# SK_MFB.net
KiCad netlist of a schematic drawn in EasyEDA Pro
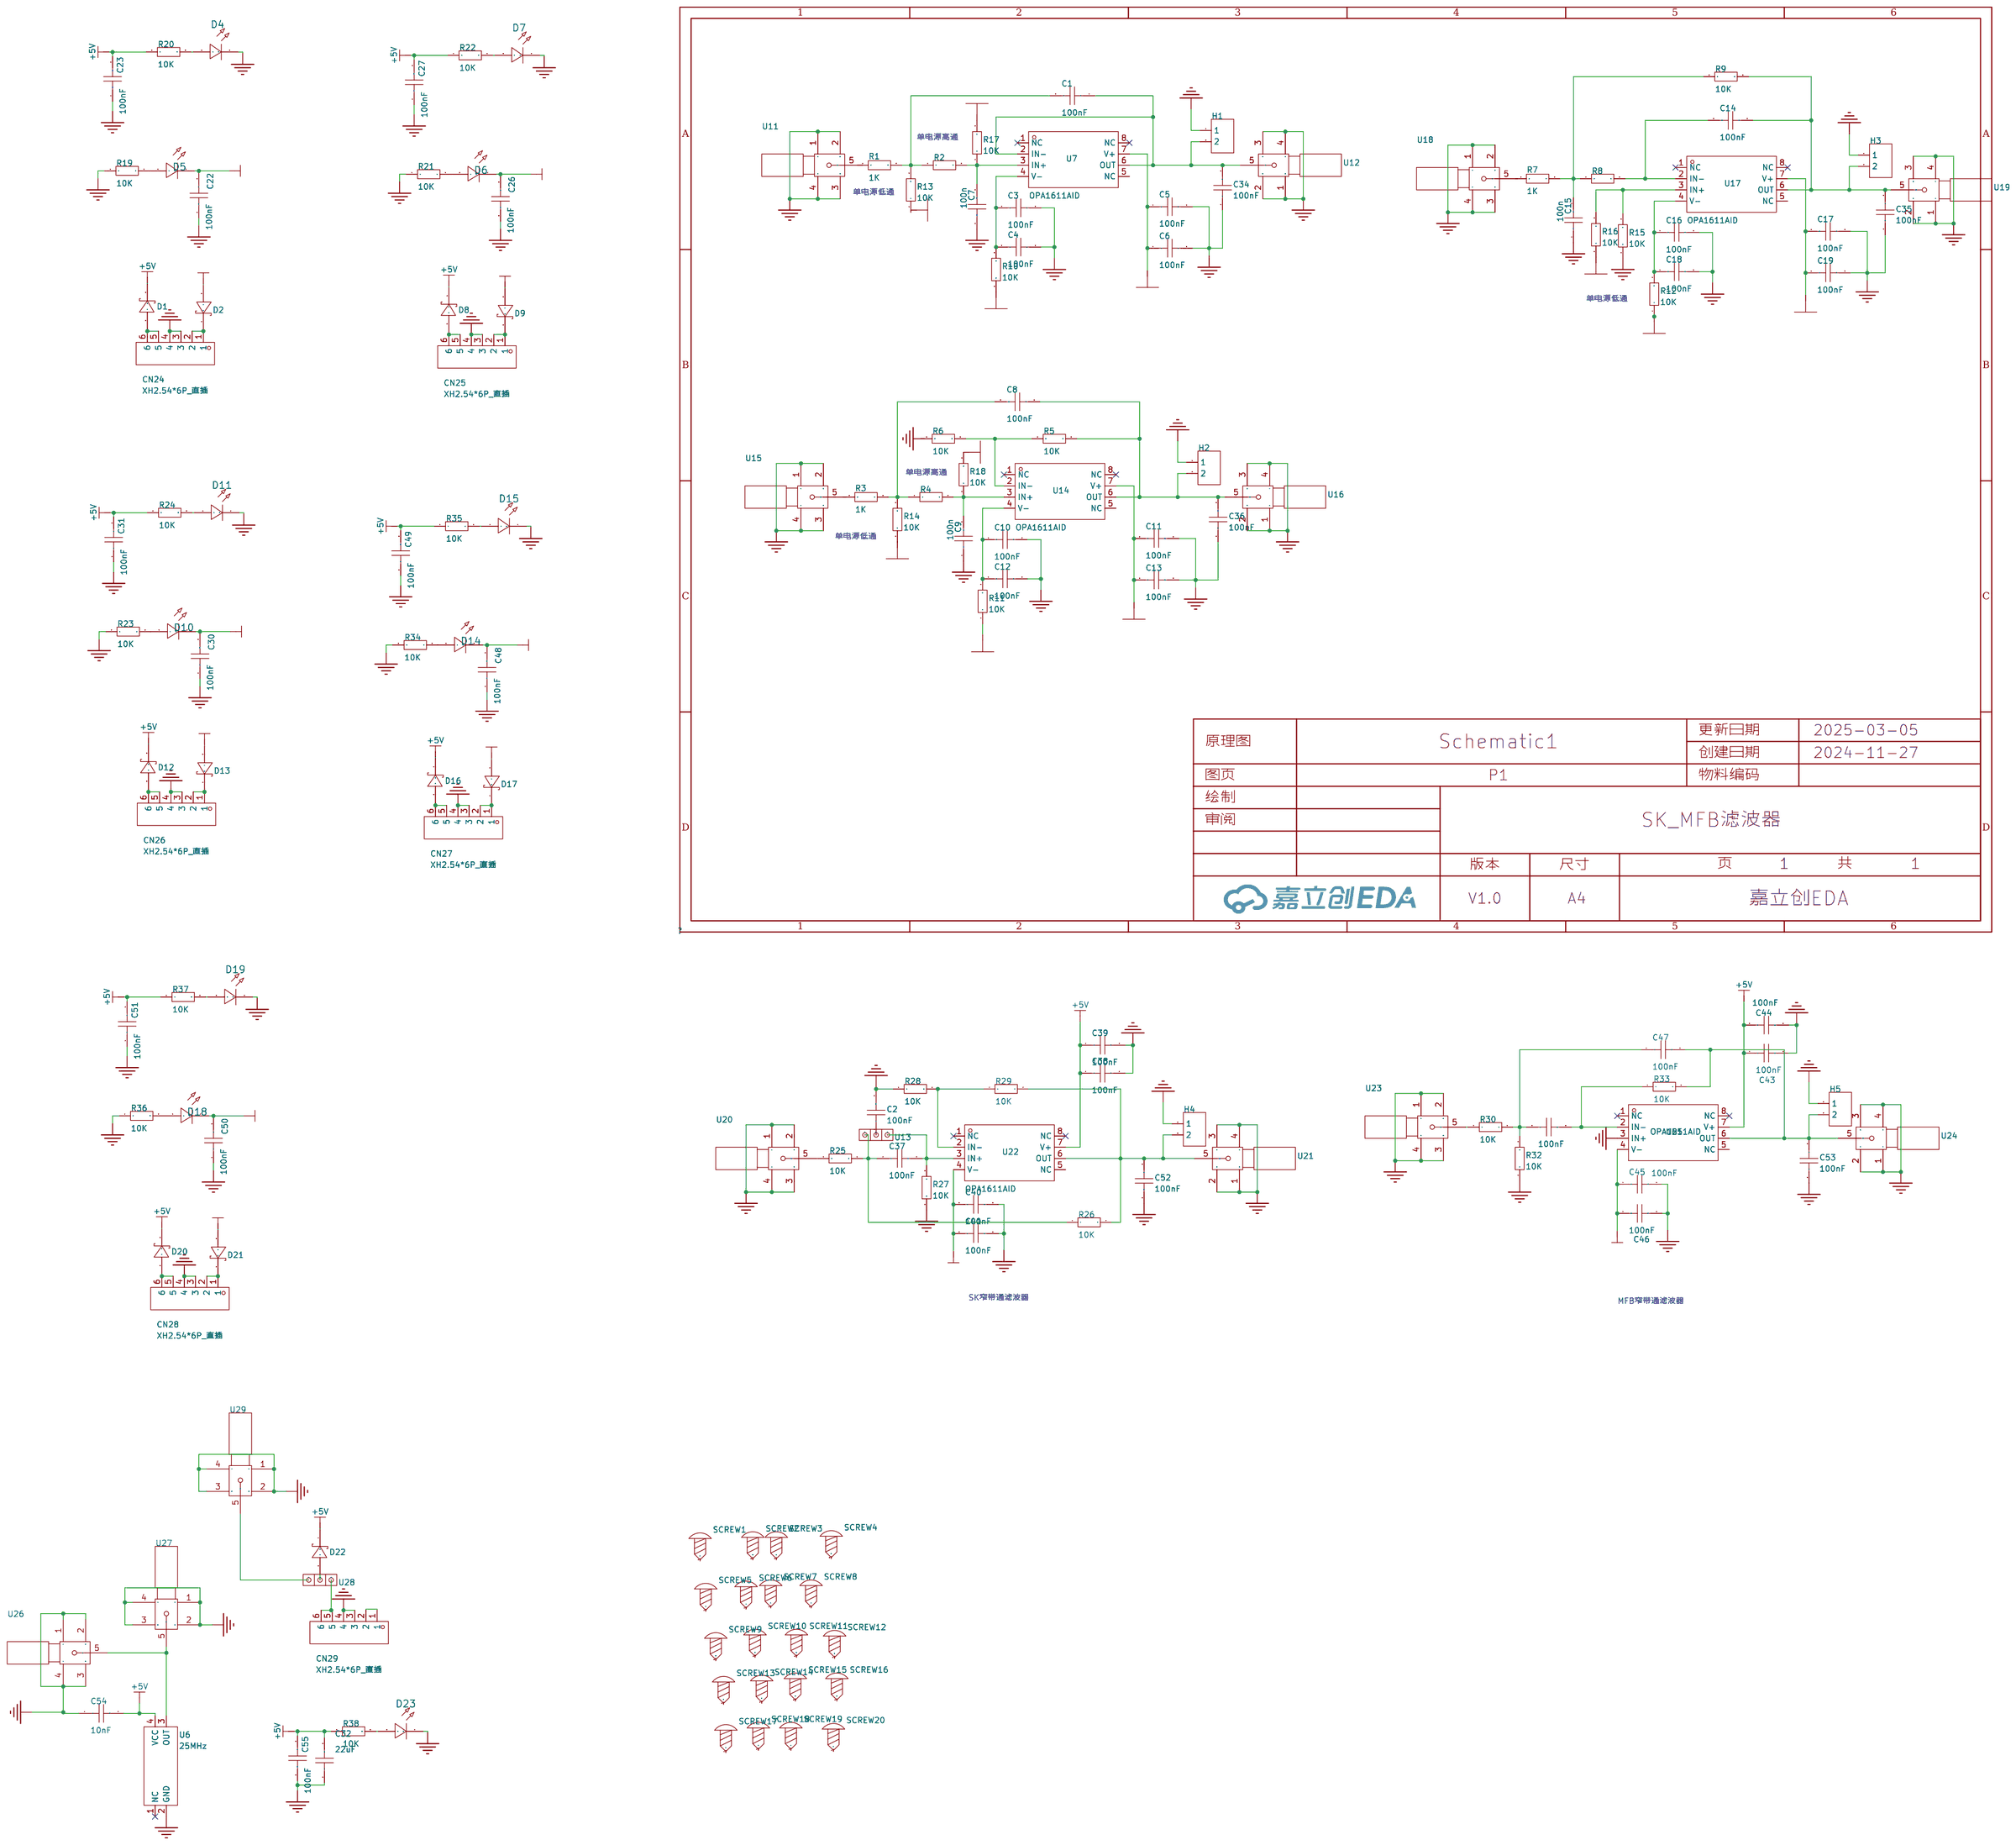
[diagram p0: schematic sheet]

(export (version "E")
  (design (tool "Eeschema 10.0.6"))
  (components
    (comp (ref "C1")
      (value "100nF")
      (footprint "easyedapro:C0805")
      (libsource (lib "easyedapro") (part "CapAcitance"))
    )
    (comp (ref "C2")
      (value "100nF")
      (footprint "easyedapro:C0805")
      (libsource (lib "easyedapro") (part "CapAcitance"))
    )
    (comp (ref "C3")
      (value "100nF")
      (footprint "easyedapro:C0805")
      (libsource (lib "easyedapro") (part "CapAcitance"))
    )
    (comp (ref "C4")
      (value "100nF")
      (footprint "easyedapro:C0805")
      (libsource (lib "easyedapro") (part "CapAcitance"))
    )
    (comp (ref "C5")
      (value "100nF")
      (footprint "easyedapro:C0805")
      (libsource (lib "easyedapro") (part "CapAcitance"))
    )
    (comp (ref "C6")
      (value "100nF")
      (footprint "easyedapro:C0805")
      (libsource (lib "easyedapro") (part "CapAcitance"))
    )
    (comp (ref "C7")
      (value "100n")
      (footprint "easyedapro:C0805")
      (libsource (lib "easyedapro") (part "CapAcitance"))
    )
    (comp (ref "C8")
      (value "100nF")
      (footprint "easyedapro:C0805")
      (libsource (lib "easyedapro") (part "CapAcitance"))
    )
    (comp (ref "C9")
      (value "100n")
      (footprint "easyedapro:C0805")
      (libsource (lib "easyedapro") (part "CapAcitance"))
    )
    (comp (ref "C10")
      (value "100nF")
      (footprint "easyedapro:C0805")
      (libsource (lib "easyedapro") (part "CapAcitance"))
    )
    (comp (ref "C11")
      (value "100nF")
      (footprint "easyedapro:C0805")
      (libsource (lib "easyedapro") (part "CapAcitance"))
    )
    (comp (ref "C12")
      (value "100nF")
      (footprint "easyedapro:C0805")
      (libsource (lib "easyedapro") (part "CapAcitance"))
    )
    (comp (ref "C13")
      (value "100nF")
      (footprint "easyedapro:C0805")
      (libsource (lib "easyedapro") (part "CapAcitance"))
    )
    (comp (ref "C14")
      (value "100nF")
      (footprint "easyedapro:C0805")
      (libsource (lib "easyedapro") (part "CapAcitance"))
    )
    (comp (ref "C15")
      (value "100n")
      (footprint "easyedapro:C0805")
      (libsource (lib "easyedapro") (part "CapAcitance"))
    )
    (comp (ref "C16")
      (value "100nF")
      (footprint "easyedapro:C0805")
      (libsource (lib "easyedapro") (part "CapAcitance"))
    )
    (comp (ref "C17")
      (value "100nF")
      (footprint "easyedapro:C0805")
      (libsource (lib "easyedapro") (part "CapAcitance"))
    )
    (comp (ref "C18")
      (value "100nF")
      (footprint "easyedapro:C0805")
      (libsource (lib "easyedapro") (part "CapAcitance"))
    )
    (comp (ref "C19")
      (value "100nF")
      (footprint "easyedapro:C0805")
      (libsource (lib "easyedapro") (part "CapAcitance"))
    )
    (comp (ref "C22")
      (value "100nF")
      (footprint "easyedapro:C0805")
      (libsource (lib "easyedapro") (part "CapAcitance"))
    )
    (comp (ref "C23")
      (value "100nF")
      (footprint "easyedapro:C0805")
      (libsource (lib "easyedapro") (part "CapAcitance"))
    )
    (comp (ref "C26")
      (value "100nF")
      (footprint "easyedapro:C0805")
      (libsource (lib "easyedapro") (part "CapAcitance"))
    )
    (comp (ref "C27")
      (value "100nF")
      (footprint "easyedapro:C0805")
      (libsource (lib "easyedapro") (part "CapAcitance"))
    )
    (comp (ref "C30")
      (value "100nF")
      (footprint "easyedapro:C0805")
      (libsource (lib "easyedapro") (part "CapAcitance"))
    )
    (comp (ref "C31")
      (value "100nF")
      (footprint "easyedapro:C0805")
      (libsource (lib "easyedapro") (part "CapAcitance"))
    )
    (comp (ref "C32")
      (value "22uF")
      (footprint "easyedapro:C1210")
      (description "容值:22uF;精度:±10%;额定电压:25V;材质(温度系数):X7R;")
      (fields
        (field (name "Manufacturer Part") "CL32B226KAJNNNE")
        (field (name "Manufacturer") "SAMSUNG(三星)")
      )
      (libsource (lib "easyedapro") (part "CL32B226KAJNNNE"))
    )
    (comp (ref "C34")
      (value "100nF")
      (footprint "easyedapro:C0805")
      (libsource (lib "easyedapro") (part "CapAcitance"))
    )
    (comp (ref "C35")
      (value "100nF")
      (footprint "easyedapro:C0805")
      (libsource (lib "easyedapro") (part "CapAcitance"))
    )
    (comp (ref "C36")
      (value "100nF")
      (footprint "easyedapro:C0805")
      (libsource (lib "easyedapro") (part "CapAcitance"))
    )
    (comp (ref "C37")
      (value "100nF")
      (footprint "easyedapro:C0805")
      (libsource (lib "easyedapro") (part "CapAcitance"))
    )
    (comp (ref "C38")
      (value "100nF")
      (footprint "easyedapro:C0805")
      (libsource (lib "easyedapro") (part "CapAcitance"))
    )
    (comp (ref "C39")
      (value "100nF")
      (footprint "easyedapro:C0805")
      (libsource (lib "easyedapro") (part "CapAcitance"))
    )
    (comp (ref "C40")
      (value "100nF")
      (footprint "easyedapro:C0805")
      (libsource (lib "easyedapro") (part "CapAcitance"))
    )
    (comp (ref "C41")
      (value "100nF")
      (footprint "easyedapro:C0805")
      (libsource (lib "easyedapro") (part "CapAcitance"))
    )
    (comp (ref "C42")
      (value "100nF")
      (footprint "easyedapro:C0805")
      (libsource (lib "easyedapro") (part "CapAcitance"))
    )
    (comp (ref "C43")
      (value "100nF")
      (footprint "easyedapro:C0805")
      (libsource (lib "easyedapro") (part "CapAcitance"))
    )
    (comp (ref "C44")
      (value "100nF")
      (footprint "easyedapro:C0805")
      (libsource (lib "easyedapro") (part "CapAcitance"))
    )
    (comp (ref "C45")
      (value "100nF")
      (footprint "easyedapro:C0805")
      (libsource (lib "easyedapro") (part "CapAcitance"))
    )
    (comp (ref "C46")
      (value "100nF")
      (footprint "easyedapro:C0805")
      (libsource (lib "easyedapro") (part "CapAcitance"))
    )
    (comp (ref "C47")
      (value "100nF")
      (footprint "easyedapro:C0805")
      (libsource (lib "easyedapro") (part "CapAcitance"))
    )
    (comp (ref "C48")
      (value "100nF")
      (footprint "easyedapro:C0805")
      (libsource (lib "easyedapro") (part "CapAcitance"))
    )
    (comp (ref "C49")
      (value "100nF")
      (footprint "easyedapro:C0805")
      (libsource (lib "easyedapro") (part "CapAcitance"))
    )
    (comp (ref "C50")
      (value "100nF")
      (footprint "easyedapro:C0805")
      (libsource (lib "easyedapro") (part "CapAcitance"))
    )
    (comp (ref "C51")
      (value "100nF")
      (footprint "easyedapro:C0805")
      (libsource (lib "easyedapro") (part "CapAcitance"))
    )
    (comp (ref "C52")
      (value "100nF")
      (footprint "easyedapro:C0805")
      (libsource (lib "easyedapro") (part "CapAcitance"))
    )
    (comp (ref "C53")
      (value "100nF")
      (footprint "easyedapro:C0805")
      (libsource (lib "easyedapro") (part "CapAcitance"))
    )
    (comp (ref "C54")
      (value "10nF")
      (footprint "easyedapro:C0805")
      (libsource (lib "easyedapro") (part "CapAcitance"))
    )
    (comp (ref "C55")
      (value "100nF")
      (footprint "easyedapro:C0805")
      (libsource (lib "easyedapro") (part "CapAcitance"))
    )
    (comp (ref "CN24")
      (value "XH2.54*6P_直插")
      (footprint "easyedapro:CONN-TH_XH2.54-6P")
      (libsource (lib "easyedapro") (part "XH2.54*6P_直插"))
    )
    (comp (ref "CN25")
      (value "XH2.54*6P_直插")
      (footprint "easyedapro:CONN-TH_XH2.54-6P")
      (libsource (lib "easyedapro") (part "XH2.54*6P_直插"))
    )
    (comp (ref "CN26")
      (value "XH2.54*6P_直插")
      (footprint "easyedapro:CONN-TH_XH2.54-6P")
      (libsource (lib "easyedapro") (part "XH2.54*6P_直插"))
    )
    (comp (ref "CN27")
      (value "XH2.54*6P_直插")
      (footprint "easyedapro:CONN-TH_XH2.54-6P")
      (libsource (lib "easyedapro") (part "XH2.54*6P_直插"))
    )
    (comp (ref "CN28")
      (value "XH2.54*6P_直插")
      (footprint "easyedapro:CONN-TH_XH2.54-6P")
      (libsource (lib "easyedapro") (part "XH2.54*6P_直插"))
    )
    (comp (ref "CN29")
      (value "XH2.54*6P_直插")
      (footprint "easyedapro:CONN-TH_XH2.54-6P")
      (libsource (lib "easyedapro") (part "XH2.54*6P_直插"))
    )
    (comp (ref "D1")
      (value "SD103AWS")
      (footprint "easyedapro:SOD-323_L1.8-W1.3-LS2.5-RD")
      (description "正向压降(Vf):600mV@200mA;直流反向耐压(Vr):40V;整流电流:350mA;")
      (fields (field (name "Manufacturer") "Hottech(合科泰)"))
      (libsource (lib "easyedapro") (part "SD103AWS_C181207"))
    )
    (comp (ref "D2")
      (value "SD103AWS")
      (footprint "easyedapro:SOD-323_L1.8-W1.3-LS2.5-RD")
      (description "正向压降(Vf):600mV@200mA;直流反向耐压(Vr):40V;整流电流:350mA;")
      (fields (field (name "Manufacturer") "Hottech(合科泰)"))
      (libsource (lib "easyedapro") (part "SD103AWS_C181207"))
    )
    (comp (ref "D4")
      (value "~")
      (footprint "easyedapro:LED_0805")
      (libsource (lib "easyedapro") (part "LED_R"))
    )
    (comp (ref "D5")
      (value "~")
      (footprint "easyedapro:LED_0805")
      (libsource (lib "easyedapro") (part "LED_R"))
    )
    (comp (ref "D6")
      (value "~")
      (footprint "easyedapro:LED_0805")
      (libsource (lib "easyedapro") (part "LED_R"))
    )
    (comp (ref "D7")
      (value "~")
      (footprint "easyedapro:LED_0805")
      (libsource (lib "easyedapro") (part "LED_R"))
    )
    (comp (ref "D8")
      (value "SD103AWS")
      (footprint "easyedapro:SOD-323_L1.8-W1.3-LS2.5-RD")
      (description "正向压降(Vf):600mV@200mA;直流反向耐压(Vr):40V;整流电流:350mA;")
      (fields (field (name "Manufacturer") "Hottech(合科泰)"))
      (libsource (lib "easyedapro") (part "SD103AWS_C181207"))
    )
    (comp (ref "D9")
      (value "SD103AWS")
      (footprint "easyedapro:SOD-323_L1.8-W1.3-LS2.5-RD")
      (description "正向压降(Vf):600mV@200mA;直流反向耐压(Vr):40V;整流电流:350mA;")
      (fields (field (name "Manufacturer") "Hottech(合科泰)"))
      (libsource (lib "easyedapro") (part "SD103AWS_C181207"))
    )
    (comp (ref "D10")
      (value "~")
      (footprint "easyedapro:LED_0805")
      (libsource (lib "easyedapro") (part "LED_R"))
    )
    (comp (ref "D11")
      (value "~")
      (footprint "easyedapro:LED_0805")
      (libsource (lib "easyedapro") (part "LED_R"))
    )
    (comp (ref "D12")
      (value "SD103AWS")
      (footprint "easyedapro:SOD-323_L1.8-W1.3-LS2.5-RD")
      (description "正向压降(Vf):600mV@200mA;直流反向耐压(Vr):40V;整流电流:350mA;")
      (fields (field (name "Manufacturer") "Hottech(合科泰)"))
      (libsource (lib "easyedapro") (part "SD103AWS_C181207"))
    )
    (comp (ref "D13")
      (value "SD103AWS")
      (footprint "easyedapro:SOD-323_L1.8-W1.3-LS2.5-RD")
      (description "正向压降(Vf):600mV@200mA;直流反向耐压(Vr):40V;整流电流:350mA;")
      (fields (field (name "Manufacturer") "Hottech(合科泰)"))
      (libsource (lib "easyedapro") (part "SD103AWS_C181207"))
    )
    (comp (ref "D14")
      (value "~")
      (footprint "easyedapro:LED_0805")
      (libsource (lib "easyedapro") (part "LED_R"))
    )
    (comp (ref "D15")
      (value "~")
      (footprint "easyedapro:LED_0805")
      (libsource (lib "easyedapro") (part "LED_R"))
    )
    (comp (ref "D16")
      (value "SD103AWS")
      (footprint "easyedapro:SOD-323_L1.8-W1.3-LS2.5-RD")
      (description "正向压降(Vf):600mV@200mA;直流反向耐压(Vr):40V;整流电流:350mA;")
      (fields (field (name "Manufacturer") "Hottech(合科泰)"))
      (libsource (lib "easyedapro") (part "SD103AWS_C181207"))
    )
    (comp (ref "D17")
      (value "SD103AWS")
      (footprint "easyedapro:SOD-323_L1.8-W1.3-LS2.5-RD")
      (description "正向压降(Vf):600mV@200mA;直流反向耐压(Vr):40V;整流电流:350mA;")
      (fields (field (name "Manufacturer") "Hottech(合科泰)"))
      (libsource (lib "easyedapro") (part "SD103AWS_C181207"))
    )
    (comp (ref "D18")
      (value "~")
      (footprint "easyedapro:LED_0805")
      (libsource (lib "easyedapro") (part "LED_R"))
    )
    (comp (ref "D19")
      (value "~")
      (footprint "easyedapro:LED_0805")
      (libsource (lib "easyedapro") (part "LED_R"))
    )
    (comp (ref "D20")
      (value "SD103AWS")
      (footprint "easyedapro:SOD-323_L1.8-W1.3-LS2.5-RD")
      (description "正向压降(Vf):600mV@200mA;直流反向耐压(Vr):40V;整流电流:350mA;")
      (fields (field (name "Manufacturer") "Hottech(合科泰)"))
      (libsource (lib "easyedapro") (part "SD103AWS_C181207"))
    )
    (comp (ref "D21")
      (value "SD103AWS")
      (footprint "easyedapro:SOD-323_L1.8-W1.3-LS2.5-RD")
      (description "正向压降(Vf):600mV@200mA;直流反向耐压(Vr):40V;整流电流:350mA;")
      (fields (field (name "Manufacturer") "Hottech(合科泰)"))
      (libsource (lib "easyedapro") (part "SD103AWS_C181207"))
    )
    (comp (ref "D22")
      (value "SD103AWS")
      (footprint "easyedapro:SOD-323_L1.8-W1.3-LS2.5-RD")
      (description "正向压降(Vf):600mV@200mA;直流反向耐压(Vr):40V;整流电流:350mA;")
      (fields (field (name "Manufacturer") "Hottech(合科泰)"))
      (libsource (lib "easyedapro") (part "SD103AWS_C181207"))
    )
    (comp (ref "D23")
      (value "~")
      (footprint "easyedapro:LED_0805")
      (libsource (lib "easyedapro") (part "LED_R"))
    )
    (comp (ref "H1")
      (value "~")
      (footprint "easyedapro:HDR-TH_2P-P2.54-V-F")
      (libsource (lib "easyedapro") (part "Header-Female-2.54_1x2"))
    )
    (comp (ref "H2")
      (value "~")
      (footprint "easyedapro:HDR-TH_2P-P2.54-V-F")
      (libsource (lib "easyedapro") (part "Header-Female-2.54_1x2"))
    )
    (comp (ref "H3")
      (value "~")
      (footprint "easyedapro:HDR-TH_2P-P2.54-V-F")
      (libsource (lib "easyedapro") (part "Header-Female-2.54_1x2"))
    )
    (comp (ref "H4")
      (value "~")
      (footprint "easyedapro:HDR-TH_2P-P2.54-V-F")
      (libsource (lib "easyedapro") (part "Header-Female-2.54_1x2"))
    )
    (comp (ref "H5")
      (value "~")
      (footprint "easyedapro:HDR-TH_2P-P2.54-V-F")
      (libsource (lib "easyedapro") (part "Header-Female-2.54_1x2"))
    )
    (comp (ref "R1") (value "1K") (footprint "easyedapro:R0603") (libsource (lib "easyedapro") (part "电阻")))
    (comp (ref "R2") (value "1K") (footprint "easyedapro:R0603") (libsource (lib "easyedapro") (part "电阻")))
    (comp (ref "R3") (value "1K") (footprint "easyedapro:R0603") (libsource (lib "easyedapro") (part "电阻")))
    (comp (ref "R4") (value "1K") (footprint "easyedapro:R0603") (libsource (lib "easyedapro") (part "电阻")))
    (comp (ref "R5") (value "10K") (footprint "easyedapro:R0603") (libsource (lib "easyedapro") (part "电阻")))
    (comp (ref "R6") (value "10K") (footprint "easyedapro:R0603") (libsource (lib "easyedapro") (part "电阻")))
    (comp (ref "R7") (value "1K") (footprint "easyedapro:R0603") (libsource (lib "easyedapro") (part "电阻")))
    (comp (ref "R8") (value "1K") (footprint "easyedapro:R0603") (libsource (lib "easyedapro") (part "电阻")))
    (comp (ref "R9") (value "10K") (footprint "easyedapro:R0603") (libsource (lib "easyedapro") (part "电阻")))
    (comp (ref "R10") (value "10K") (footprint "easyedapro:R0603") (libsource (lib "easyedapro") (part "电阻")))
    (comp (ref "R11") (value "10K") (footprint "easyedapro:R0603") (libsource (lib "easyedapro") (part "电阻")))
    (comp (ref "R12") (value "10K") (footprint "easyedapro:R0603") (libsource (lib "easyedapro") (part "电阻")))
    (comp (ref "R13") (value "10K") (footprint "easyedapro:R0603") (libsource (lib "easyedapro") (part "电阻")))
    (comp (ref "R14") (value "10K") (footprint "easyedapro:R0603") (libsource (lib "easyedapro") (part "电阻")))
    (comp (ref "R15") (value "10K") (footprint "easyedapro:R0603") (libsource (lib "easyedapro") (part "电阻")))
    (comp (ref "R16") (value "10K") (footprint "easyedapro:R0603") (libsource (lib "easyedapro") (part "电阻")))
    (comp (ref "R17") (value "10K") (footprint "easyedapro:R0603") (libsource (lib "easyedapro") (part "电阻")))
    (comp (ref "R18") (value "10K") (footprint "easyedapro:R0603") (libsource (lib "easyedapro") (part "电阻")))
    (comp (ref "R19") (value "10K") (footprint "easyedapro:R0603") (libsource (lib "easyedapro") (part "电阻")))
    (comp (ref "R20") (value "10K") (footprint "easyedapro:R0603") (libsource (lib "easyedapro") (part "电阻")))
    (comp (ref "R21") (value "10K") (footprint "easyedapro:R0603") (libsource (lib "easyedapro") (part "电阻")))
    (comp (ref "R22") (value "10K") (footprint "easyedapro:R0603") (libsource (lib "easyedapro") (part "电阻")))
    (comp (ref "R23") (value "10K") (footprint "easyedapro:R0603") (libsource (lib "easyedapro") (part "电阻")))
    (comp (ref "R24") (value "10K") (footprint "easyedapro:R0603") (libsource (lib "easyedapro") (part "电阻")))
    (comp (ref "R25") (value "10K") (footprint "easyedapro:R0603") (libsource (lib "easyedapro") (part "电阻")))
    (comp (ref "R26") (value "10K") (footprint "easyedapro:R0603") (libsource (lib "easyedapro") (part "电阻")))
    (comp (ref "R27") (value "10K") (footprint "easyedapro:R0603") (libsource (lib "easyedapro") (part "电阻")))
    (comp (ref "R28") (value "10K") (footprint "easyedapro:R0603") (libsource (lib "easyedapro") (part "电阻")))
    (comp (ref "R29") (value "10K") (footprint "easyedapro:R0603") (libsource (lib "easyedapro") (part "电阻")))
    (comp (ref "R30") (value "10K") (footprint "easyedapro:R0603") (libsource (lib "easyedapro") (part "电阻")))
    (comp (ref "R32") (value "10K") (footprint "easyedapro:R0603") (libsource (lib "easyedapro") (part "电阻")))
    (comp (ref "R33") (value "10K") (footprint "easyedapro:R0603") (libsource (lib "easyedapro") (part "电阻")))
    (comp (ref "R34") (value "10K") (footprint "easyedapro:R0603") (libsource (lib "easyedapro") (part "电阻")))
    (comp (ref "R35") (value "10K") (footprint "easyedapro:R0603") (libsource (lib "easyedapro") (part "电阻")))
    (comp (ref "R36") (value "10K") (footprint "easyedapro:R0603") (libsource (lib "easyedapro") (part "电阻")))
    (comp (ref "R37") (value "10K") (footprint "easyedapro:R0603") (libsource (lib "easyedapro") (part "电阻")))
    (comp (ref "R38") (value "10K") (footprint "easyedapro:R0603") (libsource (lib "easyedapro") (part "电阻")))
    (comp (ref "SCREW1")
      (value "~")
      (footprint "easyedapro:M3螺丝")
      (libsource (lib "easyedapro") (part "螺丝孔"))
    )
    (comp (ref "SCREW2")
      (value "~")
      (footprint "easyedapro:M3螺丝")
      (libsource (lib "easyedapro") (part "螺丝孔"))
    )
    (comp (ref "SCREW3")
      (value "~")
      (footprint "easyedapro:M3螺丝")
      (libsource (lib "easyedapro") (part "螺丝孔"))
    )
    (comp (ref "SCREW4")
      (value "~")
      (footprint "easyedapro:M3螺丝")
      (libsource (lib "easyedapro") (part "螺丝孔"))
    )
    (comp (ref "SCREW5")
      (value "~")
      (footprint "easyedapro:M3螺丝")
      (libsource (lib "easyedapro") (part "螺丝孔"))
    )
    (comp (ref "SCREW6")
      (value "~")
      (footprint "easyedapro:M3螺丝")
      (libsource (lib "easyedapro") (part "螺丝孔"))
    )
    (comp (ref "SCREW7")
      (value "~")
      (footprint "easyedapro:M3螺丝")
      (libsource (lib "easyedapro") (part "螺丝孔"))
    )
    (comp (ref "SCREW8")
      (value "~")
      (footprint "easyedapro:M3螺丝")
      (libsource (lib "easyedapro") (part "螺丝孔"))
    )
    (comp (ref "SCREW9")
      (value "~")
      (footprint "easyedapro:M3螺丝")
      (libsource (lib "easyedapro") (part "螺丝孔"))
    )
    (comp (ref "SCREW10")
      (value "~")
      (footprint "easyedapro:M3螺丝")
      (libsource (lib "easyedapro") (part "螺丝孔"))
    )
    (comp (ref "SCREW11")
      (value "~")
      (footprint "easyedapro:M3螺丝")
      (libsource (lib "easyedapro") (part "螺丝孔"))
    )
    (comp (ref "SCREW12")
      (value "~")
      (footprint "easyedapro:M3螺丝")
      (libsource (lib "easyedapro") (part "螺丝孔"))
    )
    (comp (ref "SCREW13")
      (value "~")
      (footprint "easyedapro:M3螺丝")
      (libsource (lib "easyedapro") (part "螺丝孔"))
    )
    (comp (ref "SCREW14")
      (value "~")
      (footprint "easyedapro:M3螺丝")
      (libsource (lib "easyedapro") (part "螺丝孔"))
    )
    (comp (ref "SCREW15")
      (value "~")
      (footprint "easyedapro:M3螺丝")
      (libsource (lib "easyedapro") (part "螺丝孔"))
    )
    (comp (ref "SCREW16")
      (value "~")
      (footprint "easyedapro:M3螺丝")
      (libsource (lib "easyedapro") (part "螺丝孔"))
    )
    (comp (ref "SCREW17")
      (value "~")
      (footprint "easyedapro:M3螺丝")
      (libsource (lib "easyedapro") (part "螺丝孔"))
    )
    (comp (ref "SCREW18")
      (value "~")
      (footprint "easyedapro:M3螺丝")
      (libsource (lib "easyedapro") (part "螺丝孔"))
    )
    (comp (ref "SCREW19")
      (value "~")
      (footprint "easyedapro:M3螺丝")
      (libsource (lib "easyedapro") (part "螺丝孔"))
    )
    (comp (ref "SCREW20")
      (value "~")
      (footprint "easyedapro:M3螺丝")
      (libsource (lib "easyedapro") (part "螺丝孔"))
    )
    (comp (ref "U6")
      (value "25MHz")
      (footprint "easyedapro:OSC-SMD_4P-L7.0-W5.0-BL")
      (description "频率:25MHz;输出模式:HCMOS;工作电压:3.3V;频率稳定度(全温):±50ppm;")
      (fields
        (field (name "Manufacturer Part") "CO75H4-25.000-33GDTST")
        (field (name "Manufacturer") "HCI(杭晶)")
      )
      (libsource (lib "easyedapro") (part "CO75H4-25.000-33GDTST"))
    )
    (comp (ref "U7")
      (value "OPA1611AID")
      (footprint "easyedapro:SOIC-8_L4.9-W3.9-P1.27-LS6.0-BL")
      (description "扬声器通道数:单声道;")
      (fields (field (name "Manufacturer") "TI(德州仪器)"))
      (libsource (lib "easyedapro") (part "OPA1611AID"))
    )
    (comp (ref "U11") (value "~") (footprint "easyedapro:SMA") (libsource (lib "easyedapro") (part "SMA")))
    (comp (ref "U12") (value "~") (footprint "easyedapro:SMA") (libsource (lib "easyedapro") (part "SMA")))
    (comp (ref "U13")
      (value "~")
      (footprint "easyedapro:1*3跳线")
      (libsource (lib "easyedapro") (part "1*3跳线"))
    )
    (comp (ref "U14")
      (value "OPA1611AID")
      (footprint "easyedapro:SOIC-8_L4.9-W3.9-P1.27-LS6.0-BL")
      (description "扬声器通道数:单声道;")
      (fields (field (name "Manufacturer") "TI(德州仪器)"))
      (libsource (lib "easyedapro") (part "OPA1611AID"))
    )
    (comp (ref "U15") (value "~") (footprint "easyedapro:SMA") (libsource (lib "easyedapro") (part "SMA")))
    (comp (ref "U16") (value "~") (footprint "easyedapro:SMA") (libsource (lib "easyedapro") (part "SMA")))
    (comp (ref "U17")
      (value "OPA1611AID")
      (footprint "easyedapro:SOIC-8_L4.9-W3.9-P1.27-LS6.0-BL")
      (description "扬声器通道数:单声道;")
      (fields (field (name "Manufacturer") "TI(德州仪器)"))
      (libsource (lib "easyedapro") (part "OPA1611AID"))
    )
    (comp (ref "U18") (value "~") (footprint "easyedapro:SMA") (libsource (lib "easyedapro") (part "SMA")))
    (comp (ref "U19") (value "~") (footprint "easyedapro:SMA") (libsource (lib "easyedapro") (part "SMA")))
    (comp (ref "U20") (value "~") (footprint "easyedapro:SMA") (libsource (lib "easyedapro") (part "SMA")))
    (comp (ref "U21") (value "~") (footprint "easyedapro:SMA") (libsource (lib "easyedapro") (part "SMA")))
    (comp (ref "U22")
      (value "OPA1611AID")
      (footprint "easyedapro:SOIC-8_L4.9-W3.9-P1.27-LS6.0-BL")
      (description "扬声器通道数:单声道;")
      (fields (field (name "Manufacturer") "TI(德州仪器)"))
      (libsource (lib "easyedapro") (part "OPA1611AID"))
    )
    (comp (ref "U23") (value "~") (footprint "easyedapro:SMA") (libsource (lib "easyedapro") (part "SMA")))
    (comp (ref "U24") (value "~") (footprint "easyedapro:SMA") (libsource (lib "easyedapro") (part "SMA")))
    (comp (ref "U25")
      (value "OPA1611AID")
      (footprint "easyedapro:SOIC-8_L4.9-W3.9-P1.27-LS6.0-BL")
      (description "扬声器通道数:单声道;")
      (fields (field (name "Manufacturer") "TI(德州仪器)"))
      (libsource (lib "easyedapro") (part "OPA1611AID"))
    )
    (comp (ref "U26") (value "~") (footprint "easyedapro:SMA") (libsource (lib "easyedapro") (part "SMA")))
    (comp (ref "U27") (value "~") (footprint "easyedapro:SMA") (libsource (lib "easyedapro") (part "SMA")))
    (comp (ref "U28")
      (value "~")
      (footprint "easyedapro:1*3跳线")
      (libsource (lib "easyedapro") (part "1*3跳线"))
    )
    (comp (ref "U29") (value "~") (footprint "easyedapro:SMA") (libsource (lib "easyedapro") (part "SMA")))
  )
  (nets
    (net (code "1") (name "+5V") (class "Default")
      (node (ref "C11") (pin "1") (pinfunction "1_1") (pintype "input"))
      (node (ref "C13") (pin "1") (pinfunction "1_1") (pintype "input"))
      (node (ref "C17") (pin "1") (pinfunction "1_1") (pintype "input"))
      (node (ref "C19") (pin "1") (pinfunction "1_1") (pintype "input"))
      (node (ref "C23") (pin "2") (pinfunction "2_2") (pintype "input"))
      (node (ref "C27") (pin "2") (pinfunction "2_2") (pintype "input"))
      (node (ref "C31") (pin "2") (pinfunction "2_2") (pintype "input"))
      (node (ref "C32") (pin "2") (pinfunction "2_2") (pintype "unspecified"))
      (node (ref "C38") (pin "1") (pinfunction "1_1") (pintype "input"))
      (node (ref "C39") (pin "1") (pinfunction "1_1") (pintype "input"))
      (node (ref "C43") (pin "1") (pinfunction "1_1") (pintype "input"))
      (node (ref "C44") (pin "1") (pinfunction "1_1") (pintype "input"))
      (node (ref "C49") (pin "2") (pinfunction "2_2") (pintype "input"))
      (node (ref "C5") (pin "1") (pinfunction "1_1") (pintype "input"))
      (node (ref "C51") (pin "2") (pinfunction "2_2") (pintype "input"))
      (node (ref "C54") (pin "2") (pinfunction "2_2") (pintype "input"))
      (node (ref "C55") (pin "2") (pinfunction "2_2") (pintype "input"))
      (node (ref "C6") (pin "1") (pinfunction "1_1") (pintype "input"))
      (node (ref "D1") (pin "1") (pinfunction "C_1") (pintype "unspecified"))
      (node (ref "D12") (pin "1") (pinfunction "C_1") (pintype "unspecified"))
      (node (ref "D16") (pin "1") (pinfunction "C_1") (pintype "unspecified"))
      (node (ref "D20") (pin "1") (pinfunction "C_1") (pintype "unspecified"))
      (node (ref "D22") (pin "1") (pinfunction "C_1") (pintype "unspecified"))
      (node (ref "D8") (pin "1") (pinfunction "C_1") (pintype "unspecified"))
      (node (ref "R13") (pin "1") (pinfunction "1_1") (pintype "input"))
      (node (ref "R14") (pin "1") (pinfunction "1_1") (pintype "input"))
      (node (ref "R16") (pin "1") (pinfunction "1_1") (pintype "input"))
      (node (ref "R17") (pin "2") (pinfunction "2_2") (pintype "input"))
      (node (ref "R18") (pin "2") (pinfunction "2_2") (pintype "input"))
      (node (ref "R20") (pin "1") (pinfunction "1_1") (pintype "input"))
      (node (ref "R22") (pin "1") (pinfunction "1_1") (pintype "input"))
      (node (ref "R24") (pin "1") (pinfunction "1_1") (pintype "input"))
      (node (ref "R35") (pin "1") (pinfunction "1_1") (pintype "input"))
      (node (ref "R37") (pin "1") (pinfunction "1_1") (pintype "input"))
      (node (ref "R38") (pin "1") (pinfunction "1_1") (pintype "input"))
      (node (ref "U14") (pin "7") (pinfunction "V+_7") (pintype "unspecified"))
      (node (ref "U17") (pin "7") (pinfunction "V+_7") (pintype "unspecified"))
      (node (ref "U22") (pin "7") (pinfunction "V+_7") (pintype "unspecified"))
      (node (ref "U25") (pin "7") (pinfunction "V+_7") (pintype "unspecified"))
      (node (ref "U6") (pin "4") (pinfunction "VCC_4") (pintype "unspecified"))
      (node (ref "U7") (pin "7") (pinfunction "V+_7") (pintype "unspecified"))
    )
    (net (code "2") (name "-5V") (class "Default")
      (node (ref "C22") (pin "2") (pinfunction "2_2") (pintype "input"))
      (node (ref "C26") (pin "2") (pinfunction "2_2") (pintype "input"))
      (node (ref "C30") (pin "2") (pinfunction "2_2") (pintype "input"))
      (node (ref "C40") (pin "1") (pinfunction "1_1") (pintype "input"))
      (node (ref "C41") (pin "1") (pinfunction "1_1") (pintype "input"))
      (node (ref "C45") (pin "1") (pinfunction "1_1") (pintype "input"))
      (node (ref "C46") (pin "1") (pinfunction "1_1") (pintype "input"))
      (node (ref "C48") (pin "2") (pinfunction "2_2") (pintype "input"))
      (node (ref "C50") (pin "2") (pinfunction "2_2") (pintype "input"))
      (node (ref "D10") (pin "1") (pinfunction "C_1") (pintype "input"))
      (node (ref "D13") (pin "2") (pinfunction "A_2") (pintype "unspecified"))
      (node (ref "D14") (pin "1") (pinfunction "C_1") (pintype "input"))
      (node (ref "D17") (pin "2") (pinfunction "A_2") (pintype "unspecified"))
      (node (ref "D18") (pin "1") (pinfunction "C_1") (pintype "input"))
      (node (ref "D2") (pin "2") (pinfunction "A_2") (pintype "unspecified"))
      (node (ref "D21") (pin "2") (pinfunction "A_2") (pintype "unspecified"))
      (node (ref "D5") (pin "1") (pinfunction "C_1") (pintype "input"))
      (node (ref "D6") (pin "1") (pinfunction "C_1") (pintype "input"))
      (node (ref "D9") (pin "2") (pinfunction "A_2") (pintype "unspecified"))
      (node (ref "R10") (pin "1") (pinfunction "1_1") (pintype "input"))
      (node (ref "R11") (pin "1") (pinfunction "1_1") (pintype "input"))
      (node (ref "R12") (pin "1") (pinfunction "1_1") (pintype "input"))
      (node (ref "U22") (pin "4") (pinfunction "V-_4") (pintype "unspecified"))
      (node (ref "U25") (pin "4") (pinfunction "V-_4") (pintype "unspecified"))
    )
    (net (code "3") (name "GND") (class "Default")
      (node (ref "C10") (pin "2") (pinfunction "2_2") (pintype "input"))
      (node (ref "C11") (pin "2") (pinfunction "2_2") (pintype "input"))
      (node (ref "C12") (pin "2") (pinfunction "2_2") (pintype "input"))
      (node (ref "C13") (pin "2") (pinfunction "2_2") (pintype "input"))
      (node (ref "C15") (pin "1") (pinfunction "1_1") (pintype "input"))
      (node (ref "C16") (pin "2") (pinfunction "2_2") (pintype "input"))
      (node (ref "C17") (pin "2") (pinfunction "2_2") (pintype "input"))
      (node (ref "C18") (pin "2") (pinfunction "2_2") (pintype "input"))
      (node (ref "C19") (pin "2") (pinfunction "2_2") (pintype "input"))
      (node (ref "C2") (pin "2") (pinfunction "2_2") (pintype "input"))
      (node (ref "C22") (pin "1") (pinfunction "1_1") (pintype "input"))
      (node (ref "C23") (pin "1") (pinfunction "1_1") (pintype "input"))
      (node (ref "C26") (pin "1") (pinfunction "1_1") (pintype "input"))
      (node (ref "C27") (pin "1") (pinfunction "1_1") (pintype "input"))
      (node (ref "C3") (pin "2") (pinfunction "2_2") (pintype "input"))
      (node (ref "C30") (pin "1") (pinfunction "1_1") (pintype "input"))
      (node (ref "C31") (pin "1") (pinfunction "1_1") (pintype "input"))
      (node (ref "C32") (pin "1") (pinfunction "1_1") (pintype "unspecified"))
      (node (ref "C34") (pin "1") (pinfunction "1_1") (pintype "input"))
      (node (ref "C35") (pin "1") (pinfunction "1_1") (pintype "input"))
      (node (ref "C36") (pin "1") (pinfunction "1_1") (pintype "input"))
      (node (ref "C38") (pin "2") (pinfunction "2_2") (pintype "input"))
      (node (ref "C39") (pin "2") (pinfunction "2_2") (pintype "input"))
      (node (ref "C4") (pin "2") (pinfunction "2_2") (pintype "input"))
      (node (ref "C40") (pin "2") (pinfunction "2_2") (pintype "input"))
      (node (ref "C41") (pin "2") (pinfunction "2_2") (pintype "input"))
      (node (ref "C43") (pin "2") (pinfunction "2_2") (pintype "input"))
      (node (ref "C44") (pin "2") (pinfunction "2_2") (pintype "input"))
      (node (ref "C45") (pin "2") (pinfunction "2_2") (pintype "input"))
      (node (ref "C46") (pin "2") (pinfunction "2_2") (pintype "input"))
      (node (ref "C48") (pin "1") (pinfunction "1_1") (pintype "input"))
      (node (ref "C49") (pin "1") (pinfunction "1_1") (pintype "input"))
      (node (ref "C5") (pin "2") (pinfunction "2_2") (pintype "input"))
      (node (ref "C50") (pin "1") (pinfunction "1_1") (pintype "input"))
      (node (ref "C51") (pin "1") (pinfunction "1_1") (pintype "input"))
      (node (ref "C52") (pin "1") (pinfunction "1_1") (pintype "input"))
      (node (ref "C53") (pin "1") (pinfunction "1_1") (pintype "input"))
      (node (ref "C54") (pin "1") (pinfunction "1_1") (pintype "input"))
      (node (ref "C55") (pin "1") (pinfunction "1_1") (pintype "input"))
      (node (ref "C6") (pin "2") (pinfunction "2_2") (pintype "input"))
      (node (ref "C7") (pin "1") (pinfunction "1_1") (pintype "input"))
      (node (ref "C9") (pin "1") (pinfunction "1_1") (pintype "input"))
      (node (ref "CN24") (pin "3") (pinfunction "3_3") (pintype "unspecified"))
      (node (ref "CN24") (pin "4") (pinfunction "4_4") (pintype "unspecified"))
      (node (ref "CN25") (pin "3") (pinfunction "3_3") (pintype "unspecified"))
      (node (ref "CN25") (pin "4") (pinfunction "4_4") (pintype "unspecified"))
      (node (ref "CN26") (pin "3") (pinfunction "3_3") (pintype "unspecified"))
      (node (ref "CN26") (pin "4") (pinfunction "4_4") (pintype "unspecified"))
      (node (ref "CN27") (pin "3") (pinfunction "3_3") (pintype "unspecified"))
      (node (ref "CN27") (pin "4") (pinfunction "4_4") (pintype "unspecified"))
      (node (ref "CN28") (pin "3") (pinfunction "3_3") (pintype "unspecified"))
      (node (ref "CN28") (pin "4") (pinfunction "4_4") (pintype "unspecified"))
      (node (ref "CN29") (pin "3") (pinfunction "3_3") (pintype "unspecified"))
      (node (ref "CN29") (pin "4") (pinfunction "4_4") (pintype "unspecified"))
      (node (ref "D11") (pin "1") (pinfunction "C_1") (pintype "input"))
      (node (ref "D15") (pin "1") (pinfunction "C_1") (pintype "input"))
      (node (ref "D19") (pin "1") (pinfunction "C_1") (pintype "input"))
      (node (ref "D23") (pin "1") (pinfunction "C_1") (pintype "input"))
      (node (ref "D4") (pin "1") (pinfunction "C_1") (pintype "input"))
      (node (ref "D7") (pin "1") (pinfunction "C_1") (pintype "input"))
      (node (ref "H1") (pin "1") (pinfunction "1_1") (pintype "input"))
      (node (ref "H2") (pin "1") (pinfunction "1_1") (pintype "input"))
      (node (ref "H3") (pin "1") (pinfunction "1_1") (pintype "input"))
      (node (ref "H4") (pin "1") (pinfunction "1_1") (pintype "input"))
      (node (ref "H5") (pin "1") (pinfunction "1_1") (pintype "input"))
      (node (ref "R15") (pin "1") (pinfunction "1_1") (pintype "input"))
      (node (ref "R19") (pin "1") (pinfunction "1_1") (pintype "input"))
      (node (ref "R21") (pin "1") (pinfunction "1_1") (pintype "input"))
      (node (ref "R23") (pin "1") (pinfunction "1_1") (pintype "input"))
      (node (ref "R27") (pin "1") (pinfunction "1_1") (pintype "input"))
      (node (ref "R28") (pin "1") (pinfunction "1_1") (pintype "input"))
      (node (ref "R32") (pin "1") (pinfunction "1_1") (pintype "input"))
      (node (ref "R34") (pin "1") (pinfunction "1_1") (pintype "input"))
      (node (ref "R36") (pin "1") (pinfunction "1_1") (pintype "input"))
      (node (ref "R6") (pin "1") (pinfunction "1_1") (pintype "input"))
      (node (ref "U11") (pin "1") (pinfunction "1_1") (pintype "input"))
      (node (ref "U11") (pin "2") (pinfunction "2_2") (pintype "input"))
      (node (ref "U11") (pin "3") (pinfunction "3_3") (pintype "input"))
      (node (ref "U11") (pin "4") (pinfunction "4_4") (pintype "input"))
      (node (ref "U12") (pin "1") (pinfunction "1_1") (pintype "input"))
      (node (ref "U12") (pin "2") (pinfunction "2_2") (pintype "input"))
      (node (ref "U12") (pin "3") (pinfunction "3_3") (pintype "input"))
      (node (ref "U12") (pin "4") (pinfunction "4_4") (pintype "input"))
      (node (ref "U15") (pin "1") (pinfunction "1_1") (pintype "input"))
      (node (ref "U15") (pin "2") (pinfunction "2_2") (pintype "input"))
      (node (ref "U15") (pin "3") (pinfunction "3_3") (pintype "input"))
      (node (ref "U15") (pin "4") (pinfunction "4_4") (pintype "input"))
      (node (ref "U16") (pin "1") (pinfunction "1_1") (pintype "input"))
      (node (ref "U16") (pin "2") (pinfunction "2_2") (pintype "input"))
      (node (ref "U16") (pin "3") (pinfunction "3_3") (pintype "input"))
      (node (ref "U16") (pin "4") (pinfunction "4_4") (pintype "input"))
      (node (ref "U18") (pin "1") (pinfunction "1_1") (pintype "input"))
      (node (ref "U18") (pin "2") (pinfunction "2_2") (pintype "input"))
      (node (ref "U18") (pin "3") (pinfunction "3_3") (pintype "input"))
      (node (ref "U18") (pin "4") (pinfunction "4_4") (pintype "input"))
      (node (ref "U19") (pin "1") (pinfunction "1_1") (pintype "input"))
      (node (ref "U19") (pin "2") (pinfunction "2_2") (pintype "input"))
      (node (ref "U19") (pin "3") (pinfunction "3_3") (pintype "input"))
      (node (ref "U19") (pin "4") (pinfunction "4_4") (pintype "input"))
      (node (ref "U20") (pin "1") (pinfunction "1_1") (pintype "input"))
      (node (ref "U20") (pin "2") (pinfunction "2_2") (pintype "input"))
      (node (ref "U20") (pin "3") (pinfunction "3_3") (pintype "input"))
      (node (ref "U20") (pin "4") (pinfunction "4_4") (pintype "input"))
      (node (ref "U21") (pin "1") (pinfunction "1_1") (pintype "input"))
      (node (ref "U21") (pin "2") (pinfunction "2_2") (pintype "input"))
      (node (ref "U21") (pin "3") (pinfunction "3_3") (pintype "input"))
      (node (ref "U21") (pin "4") (pinfunction "4_4") (pintype "input"))
      (node (ref "U23") (pin "1") (pinfunction "1_1") (pintype "input"))
      (node (ref "U23") (pin "2") (pinfunction "2_2") (pintype "input"))
      (node (ref "U23") (pin "3") (pinfunction "3_3") (pintype "input"))
      (node (ref "U23") (pin "4") (pinfunction "4_4") (pintype "input"))
      (node (ref "U24") (pin "1") (pinfunction "1_1") (pintype "input"))
      (node (ref "U24") (pin "2") (pinfunction "2_2") (pintype "input"))
      (node (ref "U24") (pin "3") (pinfunction "3_3") (pintype "input"))
      (node (ref "U24") (pin "4") (pinfunction "4_4") (pintype "input"))
      (node (ref "U25") (pin "3") (pinfunction "IN+_3") (pintype "unspecified"))
      (node (ref "U26") (pin "1") (pinfunction "1_1") (pintype "input"))
      (node (ref "U26") (pin "2") (pinfunction "2_2") (pintype "input"))
      (node (ref "U26") (pin "3") (pinfunction "3_3") (pintype "input"))
      (node (ref "U26") (pin "4") (pinfunction "4_4") (pintype "input"))
      (node (ref "U27") (pin "1") (pinfunction "1_1") (pintype "input"))
      (node (ref "U27") (pin "2") (pinfunction "2_2") (pintype "input"))
      (node (ref "U27") (pin "3") (pinfunction "3_3") (pintype "input"))
      (node (ref "U27") (pin "4") (pinfunction "4_4") (pintype "input"))
      (node (ref "U29") (pin "1") (pinfunction "1_1") (pintype "input"))
      (node (ref "U29") (pin "2") (pinfunction "2_2") (pintype "input"))
      (node (ref "U29") (pin "3") (pinfunction "3_3") (pintype "input"))
      (node (ref "U29") (pin "4") (pinfunction "4_4") (pintype "input"))
      (node (ref "U6") (pin "2") (pinfunction "GND_2") (pintype "unspecified"))
    )
    (net (code "4") (name "Net-(C1-Pad2)") (class "Default")
      (node (ref "C1") (pin "2") (pinfunction "2_2") (pintype "input"))
      (node (ref "R1") (pin "2") (pinfunction "2_2") (pintype "input"))
      (node (ref "R13") (pin "2") (pinfunction "2_2") (pintype "input"))
      (node (ref "R2") (pin "1") (pinfunction "1_1") (pintype "input"))
    )
    (net (code "5") (name "Net-(C2-Pad1)") (class "Default")
      (node (ref "C2") (pin "1") (pinfunction "1_1") (pintype "input"))
      (node (ref "U13") (pin "2") (pinfunction "2_2") (pintype "input"))
    )
    (net (code "6") (name "Net-(C8-Pad2)") (class "Default")
      (node (ref "C8") (pin "2") (pinfunction "2_2") (pintype "input"))
      (node (ref "R14") (pin "2") (pinfunction "2_2") (pintype "input"))
      (node (ref "R3") (pin "2") (pinfunction "2_2") (pintype "input"))
      (node (ref "R4") (pin "1") (pinfunction "1_1") (pintype "input"))
    )
    (net (code "7") (name "Net-(C15-Pad2)") (class "Default")
      (node (ref "C15") (pin "2") (pinfunction "2_2") (pintype "input"))
      (node (ref "R7") (pin "2") (pinfunction "2_2") (pintype "input"))
      (node (ref "R8") (pin "1") (pinfunction "1_1") (pintype "input"))
      (node (ref "R9") (pin "1") (pinfunction "1_1") (pintype "input"))
    )
    (net (code "8") (name "Net-(C37-Pad1)") (class "Default")
      (node (ref "C37") (pin "1") (pinfunction "1_1") (pintype "input"))
      (node (ref "R25") (pin "2") (pinfunction "2_2") (pintype "input"))
      (node (ref "R26") (pin "1") (pinfunction "1_1") (pintype "input"))
      (node (ref "U13") (pin "1") (pinfunction "1_1") (pintype "input"))
    )
    (net (code "9") (name "Net-(C42-Pad1)") (class "Default")
      (node (ref "C42") (pin "1") (pinfunction "1_1") (pintype "input"))
      (node (ref "C47") (pin "1") (pinfunction "1_1") (pintype "input"))
      (node (ref "R30") (pin "2") (pinfunction "2_2") (pintype "input"))
      (node (ref "R32") (pin "2") (pinfunction "2_2") (pintype "input"))
    )
    (net (code "10") (name "Net-(CN29-Pad1)") (class "Default")
      (node (ref "CN29") (pin "1") (pinfunction "1_1") (pintype "unspecified"))
      (node (ref "CN29") (pin "2") (pinfunction "2_2") (pintype "unspecified"))
    )
    (net (code "11") (name "Net-(CN29-Pad5)") (class "Default")
      (node (ref "CN29") (pin "5") (pinfunction "5_5") (pintype "unspecified"))
      (node (ref "CN29") (pin "6") (pinfunction "6_6") (pintype "unspecified"))
      (node (ref "U28") (pin "3") (pinfunction "3_3") (pintype "input"))
    )
    (net (code "12") (name "Net-(D1-A)") (class "Default")
      (node (ref "CN24") (pin "5") (pinfunction "5_5") (pintype "unspecified"))
      (node (ref "CN24") (pin "6") (pinfunction "6_6") (pintype "unspecified"))
      (node (ref "D1") (pin "2") (pinfunction "A_2") (pintype "unspecified"))
    )
    (net (code "13") (name "Net-(D2-C)") (class "Default")
      (node (ref "CN24") (pin "1") (pinfunction "1_1") (pintype "unspecified"))
      (node (ref "CN24") (pin "2") (pinfunction "2_2") (pintype "unspecified"))
      (node (ref "D2") (pin "1") (pinfunction "C_1") (pintype "unspecified"))
    )
    (net (code "14") (name "Net-(D4-A)") (class "Default")
      (node (ref "D4") (pin "2") (pinfunction "A_2") (pintype "input"))
      (node (ref "R20") (pin "2") (pinfunction "2_2") (pintype "input"))
    )
    (net (code "15") (name "Net-(D5-A)") (class "Default")
      (node (ref "D5") (pin "2") (pinfunction "A_2") (pintype "input"))
      (node (ref "R19") (pin "2") (pinfunction "2_2") (pintype "input"))
    )
    (net (code "16") (name "Net-(D6-A)") (class "Default")
      (node (ref "D6") (pin "2") (pinfunction "A_2") (pintype "input"))
      (node (ref "R21") (pin "2") (pinfunction "2_2") (pintype "input"))
    )
    (net (code "17") (name "Net-(D7-A)") (class "Default")
      (node (ref "D7") (pin "2") (pinfunction "A_2") (pintype "input"))
      (node (ref "R22") (pin "2") (pinfunction "2_2") (pintype "input"))
    )
    (net (code "18") (name "Net-(D8-A)") (class "Default")
      (node (ref "CN25") (pin "5") (pinfunction "5_5") (pintype "unspecified"))
      (node (ref "CN25") (pin "6") (pinfunction "6_6") (pintype "unspecified"))
      (node (ref "D8") (pin "2") (pinfunction "A_2") (pintype "unspecified"))
    )
    (net (code "19") (name "Net-(D9-C)") (class "Default")
      (node (ref "CN25") (pin "1") (pinfunction "1_1") (pintype "unspecified"))
      (node (ref "CN25") (pin "2") (pinfunction "2_2") (pintype "unspecified"))
      (node (ref "D9") (pin "1") (pinfunction "C_1") (pintype "unspecified"))
    )
    (net (code "20") (name "Net-(D10-A)") (class "Default")
      (node (ref "D10") (pin "2") (pinfunction "A_2") (pintype "input"))
      (node (ref "R23") (pin "2") (pinfunction "2_2") (pintype "input"))
    )
    (net (code "21") (name "Net-(D11-A)") (class "Default")
      (node (ref "D11") (pin "2") (pinfunction "A_2") (pintype "input"))
      (node (ref "R24") (pin "2") (pinfunction "2_2") (pintype "input"))
    )
    (net (code "22") (name "Net-(D12-A)") (class "Default")
      (node (ref "CN26") (pin "5") (pinfunction "5_5") (pintype "unspecified"))
      (node (ref "CN26") (pin "6") (pinfunction "6_6") (pintype "unspecified"))
      (node (ref "D12") (pin "2") (pinfunction "A_2") (pintype "unspecified"))
    )
    (net (code "23") (name "Net-(D13-C)") (class "Default")
      (node (ref "CN26") (pin "1") (pinfunction "1_1") (pintype "unspecified"))
      (node (ref "CN26") (pin "2") (pinfunction "2_2") (pintype "unspecified"))
      (node (ref "D13") (pin "1") (pinfunction "C_1") (pintype "unspecified"))
    )
    (net (code "24") (name "Net-(D14-A)") (class "Default")
      (node (ref "D14") (pin "2") (pinfunction "A_2") (pintype "input"))
      (node (ref "R34") (pin "2") (pinfunction "2_2") (pintype "input"))
    )
    (net (code "25") (name "Net-(D15-A)") (class "Default")
      (node (ref "D15") (pin "2") (pinfunction "A_2") (pintype "input"))
      (node (ref "R35") (pin "2") (pinfunction "2_2") (pintype "input"))
    )
    (net (code "26") (name "Net-(D16-A)") (class "Default")
      (node (ref "CN27") (pin "5") (pinfunction "5_5") (pintype "unspecified"))
      (node (ref "CN27") (pin "6") (pinfunction "6_6") (pintype "unspecified"))
      (node (ref "D16") (pin "2") (pinfunction "A_2") (pintype "unspecified"))
    )
    (net (code "27") (name "Net-(D17-C)") (class "Default")
      (node (ref "CN27") (pin "1") (pinfunction "1_1") (pintype "unspecified"))
      (node (ref "CN27") (pin "2") (pinfunction "2_2") (pintype "unspecified"))
      (node (ref "D17") (pin "1") (pinfunction "C_1") (pintype "unspecified"))
    )
    (net (code "28") (name "Net-(D18-A)") (class "Default")
      (node (ref "D18") (pin "2") (pinfunction "A_2") (pintype "input"))
      (node (ref "R36") (pin "2") (pinfunction "2_2") (pintype "input"))
    )
    (net (code "29") (name "Net-(D19-A)") (class "Default")
      (node (ref "D19") (pin "2") (pinfunction "A_2") (pintype "input"))
      (node (ref "R37") (pin "2") (pinfunction "2_2") (pintype "input"))
    )
    (net (code "30") (name "Net-(D20-A)") (class "Default")
      (node (ref "CN28") (pin "5") (pinfunction "5_5") (pintype "unspecified"))
      (node (ref "CN28") (pin "6") (pinfunction "6_6") (pintype "unspecified"))
      (node (ref "D20") (pin "2") (pinfunction "A_2") (pintype "unspecified"))
    )
    (net (code "31") (name "Net-(D21-C)") (class "Default")
      (node (ref "CN28") (pin "1") (pinfunction "1_1") (pintype "unspecified"))
      (node (ref "CN28") (pin "2") (pinfunction "2_2") (pintype "unspecified"))
      (node (ref "D21") (pin "1") (pinfunction "C_1") (pintype "unspecified"))
    )
    (net (code "32") (name "Net-(D22-A)") (class "Default")
      (node (ref "D22") (pin "2") (pinfunction "A_2") (pintype "unspecified"))
      (node (ref "U28") (pin "2") (pinfunction "2_2") (pintype "input"))
    )
    (net (code "33") (name "Net-(D23-A)") (class "Default")
      (node (ref "D23") (pin "2") (pinfunction "A_2") (pintype "input"))
      (node (ref "R38") (pin "2") (pinfunction "2_2") (pintype "input"))
    )
    (net (code "34") (name "Net-(R1-Pad1)") (class "Default")
      (node (ref "R1") (pin "1") (pinfunction "1_1") (pintype "input"))
      (node (ref "U11") (pin "5") (pinfunction "5_5") (pintype "input"))
    )
    (net (code "35") (name "Net-(R3-Pad1)") (class "Default")
      (node (ref "R3") (pin "1") (pinfunction "1_1") (pintype "input"))
      (node (ref "U15") (pin "5") (pinfunction "5_5") (pintype "input"))
    )
    (net (code "36") (name "Net-(R7-Pad1)") (class "Default")
      (node (ref "R7") (pin "1") (pinfunction "1_1") (pintype "input"))
      (node (ref "U18") (pin "5") (pinfunction "5_5") (pintype "input"))
    )
    (net (code "37") (name "Net-(R25-Pad1)") (class "Default")
      (node (ref "R25") (pin "1") (pinfunction "1_1") (pintype "input"))
      (node (ref "U20") (pin "5") (pinfunction "5_5") (pintype "input"))
    )
    (net (code "38") (name "Net-(R30-Pad1)") (class "Default")
      (node (ref "R30") (pin "1") (pinfunction "1_1") (pintype "input"))
      (node (ref "U23") (pin "5") (pinfunction "5_5") (pintype "input"))
    )
    (net (code "39") (name "Net-(U6-OUT)") (class "Default")
      (node (ref "U26") (pin "5") (pinfunction "5_5") (pintype "input"))
      (node (ref "U27") (pin "5") (pinfunction "5_5") (pintype "input"))
      (node (ref "U6") (pin "3") (pinfunction "OUT_3") (pintype "unspecified"))
    )
    (net (code "40") (name "Net-(U7-IN+)") (class "Default")
      (node (ref "C7") (pin "2") (pinfunction "2_2") (pintype "input"))
      (node (ref "R17") (pin "1") (pinfunction "1_1") (pintype "input"))
      (node (ref "R2") (pin "2") (pinfunction "2_2") (pintype "input"))
      (node (ref "U7") (pin "3") (pinfunction "IN+_3") (pintype "unspecified"))
    )
    (net (code "41") (name "Net-(U7-IN-)") (class "Default")
      (node (ref "C1") (pin "1") (pinfunction "1_1") (pintype "input"))
      (node (ref "C34") (pin "2") (pinfunction "2_2") (pintype "input"))
      (node (ref "H1") (pin "2") (pinfunction "2_2") (pintype "input"))
      (node (ref "U12") (pin "5") (pinfunction "5_5") (pintype "input"))
      (node (ref "U7") (pin "2") (pinfunction "IN-_2") (pintype "unspecified"))
      (node (ref "U7") (pin "6") (pinfunction "OUT_6") (pintype "unspecified"))
    )
    (net (code "42") (name "Net-(U7-V-)") (class "Default")
      (node (ref "C3") (pin "1") (pinfunction "1_1") (pintype "input"))
      (node (ref "C4") (pin "1") (pinfunction "1_1") (pintype "input"))
      (node (ref "R10") (pin "2") (pinfunction "2_2") (pintype "input"))
      (node (ref "U7") (pin "4") (pinfunction "V-_4") (pintype "unspecified"))
    )
    (net (code "43") (name "Net-(U14-IN+)") (class "Default")
      (node (ref "C9") (pin "2") (pinfunction "2_2") (pintype "input"))
      (node (ref "R18") (pin "1") (pinfunction "1_1") (pintype "input"))
      (node (ref "R4") (pin "2") (pinfunction "2_2") (pintype "input"))
      (node (ref "U14") (pin "3") (pinfunction "IN+_3") (pintype "unspecified"))
    )
    (net (code "44") (name "Net-(U14-IN-)") (class "Default")
      (node (ref "R5") (pin "1") (pinfunction "1_1") (pintype "input"))
      (node (ref "R6") (pin "2") (pinfunction "2_2") (pintype "input"))
      (node (ref "U14") (pin "2") (pinfunction "IN-_2") (pintype "unspecified"))
    )
    (net (code "45") (name "Net-(U14-OUT)") (class "Default")
      (node (ref "C36") (pin "2") (pinfunction "2_2") (pintype "input"))
      (node (ref "C8") (pin "1") (pinfunction "1_1") (pintype "input"))
      (node (ref "H2") (pin "2") (pinfunction "2_2") (pintype "input"))
      (node (ref "R5") (pin "2") (pinfunction "2_2") (pintype "input"))
      (node (ref "U14") (pin "6") (pinfunction "OUT_6") (pintype "unspecified"))
      (node (ref "U16") (pin "5") (pinfunction "5_5") (pintype "input"))
    )
    (net (code "46") (name "Net-(U14-V-)") (class "Default")
      (node (ref "C10") (pin "1") (pinfunction "1_1") (pintype "input"))
      (node (ref "C12") (pin "1") (pinfunction "1_1") (pintype "input"))
      (node (ref "R11") (pin "2") (pinfunction "2_2") (pintype "input"))
      (node (ref "U14") (pin "4") (pinfunction "V-_4") (pintype "unspecified"))
    )
    (net (code "47") (name "Net-(U17-IN+)") (class "Default")
      (node (ref "R15") (pin "2") (pinfunction "2_2") (pintype "input"))
      (node (ref "R16") (pin "2") (pinfunction "2_2") (pintype "input"))
      (node (ref "U17") (pin "3") (pinfunction "IN+_3") (pintype "unspecified"))
    )
    (net (code "48") (name "Net-(U17-IN-)") (class "Default")
      (node (ref "C14") (pin "2") (pinfunction "2_2") (pintype "input"))
      (node (ref "R8") (pin "2") (pinfunction "2_2") (pintype "input"))
      (node (ref "U17") (pin "2") (pinfunction "IN-_2") (pintype "unspecified"))
    )
    (net (code "49") (name "Net-(U17-OUT)") (class "Default")
      (node (ref "C14") (pin "1") (pinfunction "1_1") (pintype "input"))
      (node (ref "C35") (pin "2") (pinfunction "2_2") (pintype "input"))
      (node (ref "H3") (pin "2") (pinfunction "2_2") (pintype "input"))
      (node (ref "R9") (pin "2") (pinfunction "2_2") (pintype "input"))
      (node (ref "U17") (pin "6") (pinfunction "OUT_6") (pintype "unspecified"))
      (node (ref "U19") (pin "5") (pinfunction "5_5") (pintype "input"))
    )
    (net (code "50") (name "Net-(U17-V-)") (class "Default")
      (node (ref "C16") (pin "1") (pinfunction "1_1") (pintype "input"))
      (node (ref "C18") (pin "1") (pinfunction "1_1") (pintype "input"))
      (node (ref "R12") (pin "2") (pinfunction "2_2") (pintype "input"))
      (node (ref "U17") (pin "4") (pinfunction "V-_4") (pintype "unspecified"))
    )
    (net (code "51") (name "Net-(U22-IN+)") (class "Default")
      (node (ref "C37") (pin "2") (pinfunction "2_2") (pintype "input"))
      (node (ref "R27") (pin "2") (pinfunction "2_2") (pintype "input"))
      (node (ref "U13") (pin "3") (pinfunction "3_3") (pintype "input"))
      (node (ref "U22") (pin "3") (pinfunction "IN+_3") (pintype "unspecified"))
    )
    (net (code "52") (name "Net-(U22-IN-)") (class "Default")
      (node (ref "R28") (pin "2") (pinfunction "2_2") (pintype "input"))
      (node (ref "R29") (pin "1") (pinfunction "1_1") (pintype "input"))
      (node (ref "U22") (pin "2") (pinfunction "IN-_2") (pintype "unspecified"))
    )
    (net (code "53") (name "Net-(U22-OUT)") (class "Default")
      (node (ref "C52") (pin "2") (pinfunction "2_2") (pintype "input"))
      (node (ref "H4") (pin "2") (pinfunction "2_2") (pintype "input"))
      (node (ref "R26") (pin "2") (pinfunction "2_2") (pintype "input"))
      (node (ref "R29") (pin "2") (pinfunction "2_2") (pintype "input"))
      (node (ref "U21") (pin "5") (pinfunction "5_5") (pintype "input"))
      (node (ref "U22") (pin "6") (pinfunction "OUT_6") (pintype "unspecified"))
    )
    (net (code "54") (name "Net-(U25-IN-)") (class "Default")
      (node (ref "C42") (pin "2") (pinfunction "2_2") (pintype "input"))
      (node (ref "R33") (pin "1") (pinfunction "1_1") (pintype "input"))
      (node (ref "U25") (pin "2") (pinfunction "IN-_2") (pintype "unspecified"))
    )
    (net (code "55") (name "Net-(U25-OUT)") (class "Default")
      (node (ref "C47") (pin "2") (pinfunction "2_2") (pintype "input"))
      (node (ref "C53") (pin "2") (pinfunction "2_2") (pintype "input"))
      (node (ref "H5") (pin "2") (pinfunction "2_2") (pintype "input"))
      (node (ref "R33") (pin "2") (pinfunction "2_2") (pintype "input"))
      (node (ref "U24") (pin "5") (pinfunction "5_5") (pintype "input"))
      (node (ref "U25") (pin "6") (pinfunction "OUT_6") (pintype "unspecified"))
    )
    (net (code "56") (name "Net-(U28-Pad1)") (class "Default")
      (node (ref "U28") (pin "1") (pinfunction "1_1") (pintype "input"))
      (node (ref "U29") (pin "5") (pinfunction "5_5") (pintype "input"))
    )
    (net (code "57") (name "unconnected-(SCREW1-Pad1)") (class "Default")
      (node (ref "SCREW1") (pin "1") (pinfunction "1_1") (pintype "input"))
    )
    (net (code "58") (name "unconnected-(SCREW2-Pad1)") (class "Default")
      (node (ref "SCREW2") (pin "1") (pinfunction "1_1") (pintype "input"))
    )
    (net (code "59") (name "unconnected-(SCREW3-Pad1)") (class "Default")
      (node (ref "SCREW3") (pin "1") (pinfunction "1_1") (pintype "input"))
    )
    (net (code "60") (name "unconnected-(SCREW4-Pad1)") (class "Default")
      (node (ref "SCREW4") (pin "1") (pinfunction "1_1") (pintype "input"))
    )
    (net (code "61") (name "unconnected-(SCREW5-Pad1)") (class "Default")
      (node (ref "SCREW5") (pin "1") (pinfunction "1_1") (pintype "input"))
    )
    (net (code "62") (name "unconnected-(SCREW6-Pad1)") (class "Default")
      (node (ref "SCREW6") (pin "1") (pinfunction "1_1") (pintype "input"))
    )
    (net (code "63") (name "unconnected-(SCREW7-Pad1)") (class "Default")
      (node (ref "SCREW7") (pin "1") (pinfunction "1_1") (pintype "input"))
    )
    (net (code "64") (name "unconnected-(SCREW8-Pad1)") (class "Default")
      (node (ref "SCREW8") (pin "1") (pinfunction "1_1") (pintype "input"))
    )
    (net (code "65") (name "unconnected-(SCREW9-Pad1)") (class "Default")
      (node (ref "SCREW9") (pin "1") (pinfunction "1_1") (pintype "input"))
    )
    (net (code "66") (name "unconnected-(SCREW10-Pad1)") (class "Default")
      (node (ref "SCREW10") (pin "1") (pinfunction "1_1") (pintype "input"))
    )
    (net (code "67") (name "unconnected-(SCREW11-Pad1)") (class "Default")
      (node (ref "SCREW11") (pin "1") (pinfunction "1_1") (pintype "input"))
    )
    (net (code "68") (name "unconnected-(SCREW12-Pad1)") (class "Default")
      (node (ref "SCREW12") (pin "1") (pinfunction "1_1") (pintype "input"))
    )
    (net (code "69") (name "unconnected-(SCREW13-Pad1)") (class "Default")
      (node (ref "SCREW13") (pin "1") (pinfunction "1_1") (pintype "input"))
    )
    (net (code "70") (name "unconnected-(SCREW14-Pad1)") (class "Default")
      (node (ref "SCREW14") (pin "1") (pinfunction "1_1") (pintype "input"))
    )
    (net (code "71") (name "unconnected-(SCREW15-Pad1)") (class "Default")
      (node (ref "SCREW15") (pin "1") (pinfunction "1_1") (pintype "input"))
    )
    (net (code "72") (name "unconnected-(SCREW16-Pad1)") (class "Default")
      (node (ref "SCREW16") (pin "1") (pinfunction "1_1") (pintype "input"))
    )
    (net (code "73") (name "unconnected-(SCREW17-Pad1)") (class "Default")
      (node (ref "SCREW17") (pin "1") (pinfunction "1_1") (pintype "input"))
    )
    (net (code "74") (name "unconnected-(SCREW18-Pad1)") (class "Default")
      (node (ref "SCREW18") (pin "1") (pinfunction "1_1") (pintype "input"))
    )
    (net (code "75") (name "unconnected-(SCREW19-Pad1)") (class "Default")
      (node (ref "SCREW19") (pin "1") (pinfunction "1_1") (pintype "input"))
    )
    (net (code "76") (name "unconnected-(SCREW20-Pad1)") (class "Default")
      (node (ref "SCREW20") (pin "1") (pinfunction "1_1") (pintype "input"))
    )
    (net (code "77") (name "unconnected-(U6-NC-Pad1)") (class "Default")
      (node (ref "U6") (pin "1") (pinfunction "NC_1") (pintype "unspecified+no_connect"))
    )
    (net (code "78") (name "unconnected-(U7-NC-Pad1)") (class "Default")
      (node (ref "U7") (pin "1") (pinfunction "NC_1") (pintype "unspecified+no_connect"))
    )
    (net (code "79") (name "unconnected-(U7-NC-Pad5)") (class "Default")
      (node (ref "U7") (pin "5") (pinfunction "NC_5") (pintype "unspecified"))
    )
    (net (code "80") (name "unconnected-(U7-NC-Pad8)") (class "Default")
      (node (ref "U7") (pin "8") (pinfunction "NC_8") (pintype "unspecified+no_connect"))
    )
    (net (code "81") (name "unconnected-(U14-NC-Pad1)") (class "Default")
      (node (ref "U14") (pin "1") (pinfunction "NC_1") (pintype "unspecified+no_connect"))
    )
    (net (code "82") (name "unconnected-(U14-NC-Pad5)") (class "Default")
      (node (ref "U14") (pin "5") (pinfunction "NC_5") (pintype "unspecified"))
    )
    (net (code "83") (name "unconnected-(U14-NC-Pad8)") (class "Default")
      (node (ref "U14") (pin "8") (pinfunction "NC_8") (pintype "unspecified+no_connect"))
    )
    (net (code "84") (name "unconnected-(U17-NC-Pad1)") (class "Default")
      (node (ref "U17") (pin "1") (pinfunction "NC_1") (pintype "unspecified+no_connect"))
    )
    (net (code "85") (name "unconnected-(U17-NC-Pad5)") (class "Default")
      (node (ref "U17") (pin "5") (pinfunction "NC_5") (pintype "unspecified"))
    )
    (net (code "86") (name "unconnected-(U17-NC-Pad8)") (class "Default")
      (node (ref "U17") (pin "8") (pinfunction "NC_8") (pintype "unspecified+no_connect"))
    )
    (net (code "87") (name "unconnected-(U22-NC-Pad1)") (class "Default")
      (node (ref "U22") (pin "1") (pinfunction "NC_1") (pintype "unspecified+no_connect"))
    )
    (net (code "88") (name "unconnected-(U22-NC-Pad5)") (class "Default")
      (node (ref "U22") (pin "5") (pinfunction "NC_5") (pintype "unspecified"))
    )
    (net (code "89") (name "unconnected-(U22-NC-Pad8)") (class "Default")
      (node (ref "U22") (pin "8") (pinfunction "NC_8") (pintype "unspecified+no_connect"))
    )
    (net (code "90") (name "unconnected-(U25-NC-Pad1)") (class "Default")
      (node (ref "U25") (pin "1") (pinfunction "NC_1") (pintype "unspecified+no_connect"))
    )
    (net (code "91") (name "unconnected-(U25-NC-Pad5)") (class "Default")
      (node (ref "U25") (pin "5") (pinfunction "NC_5") (pintype "unspecified"))
    )
    (net (code "92") (name "unconnected-(U25-NC-Pad8)") (class "Default")
      (node (ref "U25") (pin "8") (pinfunction "NC_8") (pintype "unspecified+no_connect"))
    )
  )
)
